# ATACS_SCH.net
KiCad netlist of a schematic drawn in Altium Designer
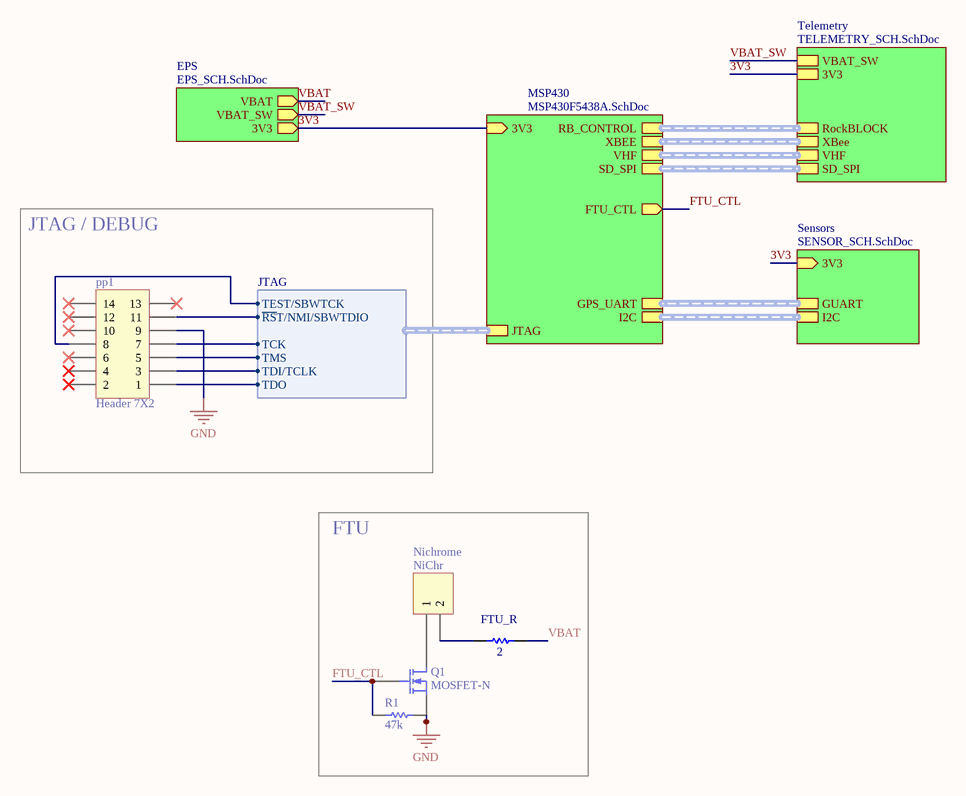
[diagram p0: ATACS_SCH.SchDoc]

(export (version "E")
  (design (tool "Eeschema 10.0.6"))
  (components
    (comp (ref "FTU_R")
      (value "2")
      (footprint "*RES_SMW52R0JT")
      (description "Resistive element")
      (fields (field (name "Comment") "Resistor"))
      (libsource (lib "MXLab Generic") (part "Resistor"))
    )
    (comp (ref "NiChr")
      (value "Nichrome")
      (footprint "Nichrome")
      (description "Header, 2-Pin")
      (fields (field (name "PUBLISHER") "Altium Limited"))
      (libsource (lib "Miscellaneous Connectors") (part "Header 2"))
    )
    (comp (ref "pp1")
      (value "Header 7X2")
      (footprint "HDR2X7")
      (description "Header, 7-Pin, Dual row")
      (fields (field (name "PUBLISHER") "Altium Limited"))
      (libsource (lib "Miscellaneous Connectors") (part "Header 7X2"))
    )
    (comp (ref "Q1")
      (value "MOSFET-N")
      (footprint "MOSFET")
      (description "N-Channel MOSFET")
      (fields (field (name "PUBLISHER") "Altium Limited"))
      (libsource (lib "Miscellaneous Devices") (part "MOSFET-N"))
    )
    (comp (ref "R1")
      (value "47k")
      (footprint "J1-0603")
      (description "Resistive element")
      (fields (field (name "Comment") "Resistor"))
      (libsource (lib "MXLab Generic") (part "Resistor"))
    )
  )
  (nets
    (net (code "3") (name "/FTU_CTL") (class "Default")
      (node (ref "Q1") (pin "2") (pinfunction "G_2") (pintype "passive"))
      (node (ref "R1") (pin "1") (pinfunction "1_1") (pintype "passive"))
    )
    (net (code "8") (name "/TCK") (class "Default")
      (node (ref "pp1") (pin "7") (pinfunction "7_7") (pintype "passive"))
    )
    (net (code "9") (name "/TDI{slash}TCLK") (class "Default")
      (node (ref "pp1") (pin "3") (pinfunction "3_3") (pintype "passive"))
    )
    (net (code "10") (name "/TDO") (class "Default")
      (node (ref "pp1") (pin "1") (pinfunction "1_1") (pintype "passive"))
    )
    (net (code "11") (name "/TEST{slash}SBWTCK") (class "Default")
      (node (ref "pp1") (pin "8") (pinfunction "8_8") (pintype "passive"))
    )
    (net (code "12") (name "/TMS") (class "Default")
      (node (ref "pp1") (pin "5") (pinfunction "5_5") (pintype "passive"))
    )
    (net (code "13") (name "/VBAT") (class "Default")
      (node (ref "FTU_R") (pin "2") (pinfunction "2_2") (pintype "passive"))
    )
    (net (code "18") (name "/~{RS}T{slash}NMI{slash}SBWTDIO") (class "Default")
      (node (ref "pp1") (pin "11") (pinfunction "11_11") (pintype "passive"))
    )
    (net (code "19") (name "GND") (class "Default")
      (node (ref "Q1") (pin "3") (pinfunction "S_3") (pintype "passive"))
      (node (ref "R1") (pin "2") (pinfunction "2_2") (pintype "passive"))
      (node (ref "pp1") (pin "9") (pinfunction "9_9") (pintype "passive"))
    )
    (net (code "20") (name "Net-(FTU_R-Pad1)") (class "Default")
      (node (ref "FTU_R") (pin "1") (pinfunction "1_1") (pintype "passive"))
      (node (ref "NiChr") (pin "2") (pinfunction "2_2") (pintype "passive"))
    )
    (net (code "21") (name "Net-(Q1-D)") (class "Default")
      (node (ref "NiChr") (pin "1") (pinfunction "1_1") (pintype "passive"))
      (node (ref "Q1") (pin "1") (pinfunction "D_1") (pintype "passive"))
    )
    (net (code "22") (name "unconnected-(pp1-Pad2)") (class "Default")
      (node (ref "pp1") (pin "2") (pinfunction "2_2") (pintype "passive+no_connect"))
    )
    (net (code "23") (name "unconnected-(pp1-Pad4)") (class "Default")
      (node (ref "pp1") (pin "4") (pinfunction "4_4") (pintype "passive+no_connect"))
    )
    (net (code "24") (name "unconnected-(pp1-Pad6)") (class "Default")
      (node (ref "pp1") (pin "6") (pinfunction "6_6") (pintype "passive+no_connect"))
    )
    (net (code "25") (name "unconnected-(pp1-Pad10)") (class "Default")
      (node (ref "pp1") (pin "10") (pinfunction "10_10") (pintype "passive+no_connect"))
    )
    (net (code "26") (name "unconnected-(pp1-Pad12)") (class "Default")
      (node (ref "pp1") (pin "12") (pinfunction "12_12") (pintype "passive+no_connect"))
    )
    (net (code "27") (name "unconnected-(pp1-Pad13)") (class "Default")
      (node (ref "pp1") (pin "13") (pinfunction "13_13") (pintype "passive+no_connect"))
    )
    (net (code "28") (name "unconnected-(pp1-Pad14)") (class "Default")
      (node (ref "pp1") (pin "14") (pinfunction "14_14") (pintype "passive+no_connect"))
    )
  )
)
